# Converter_board.net
KiCad netlist of a schematic drawn in EAGLE
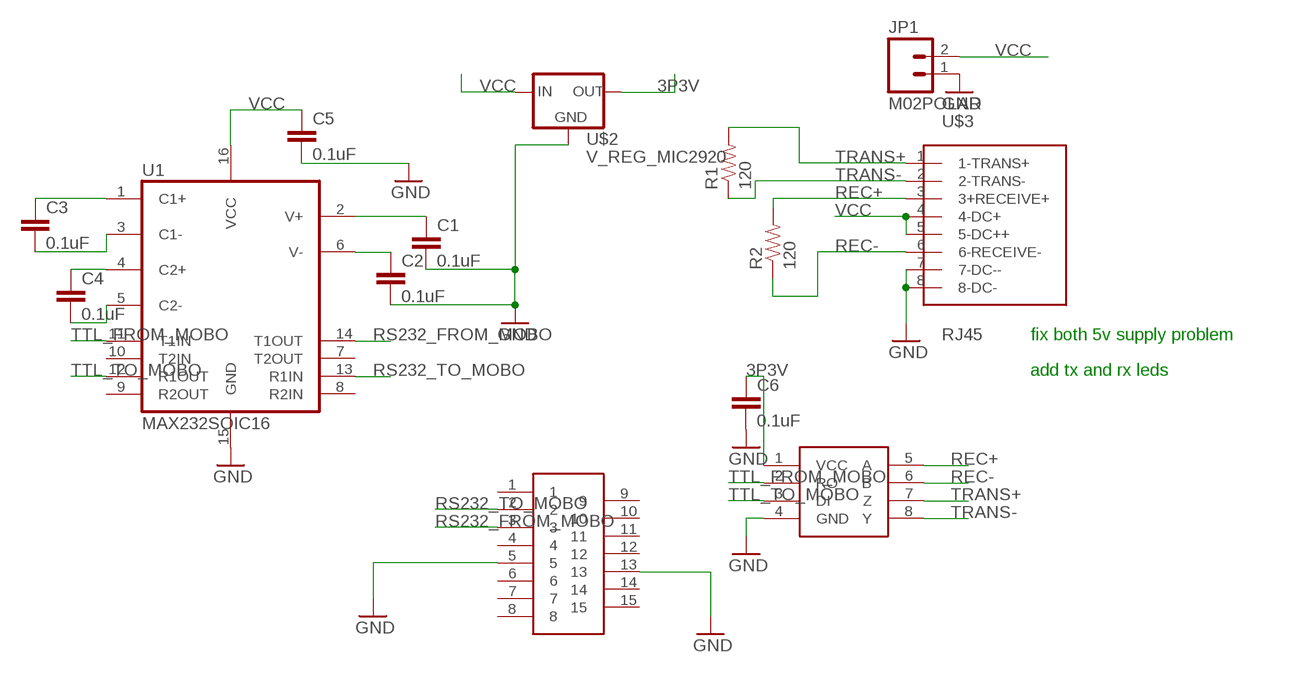
[diagram p0: schematic, sheet 1]

(export (version "E")
  (design (tool "Eeschema 10.0.6"))
  (components
    (comp (ref "C1")
      (value "0.1uF")
      (footprint "eagle-import:1206")
      (libsource (lib "eagle-import") (part "CAP1206"))
    )
    (comp (ref "C2")
      (value "0.1uF")
      (footprint "eagle-import:1206")
      (libsource (lib "eagle-import") (part "CAP1206"))
    )
    (comp (ref "C3")
      (value "0.1uF")
      (footprint "eagle-import:1206")
      (libsource (lib "eagle-import") (part "CAP1206"))
    )
    (comp (ref "C4")
      (value "0.1uF")
      (footprint "eagle-import:1206")
      (libsource (lib "eagle-import") (part "CAP1206"))
    )
    (comp (ref "C5")
      (value "0.1uF")
      (footprint "eagle-import:1206")
      (libsource (lib "eagle-import") (part "CAP1206"))
    )
    (comp (ref "C6")
      (value "0.1uF")
      (footprint "eagle-import:1206")
      (libsource (lib "eagle-import") (part "CAP1206"))
    )
    (comp (ref "JP1")
      (value "M02POLAR")
      (footprint "eagle-import:MOLEX-1X2")
      (libsource (lib "eagle-import") (part "M02POLAR"))
    )
    (comp (ref "R1")
      (value "120")
      (footprint "eagle-import:1206")
      (libsource (lib "eagle-import") (part "RESISTOR1206"))
    )
    (comp (ref "R2")
      (value "120")
      (footprint "eagle-import:1206")
      (libsource (lib "eagle-import") (part "RESISTOR1206"))
    )
    (comp (ref "U$1")
      (value "MAX3077ESA")
      (footprint "eagle-import:SOIC8")
      (libsource (lib "eagle-import") (part "MAX3077ESA"))
    )
    (comp (ref "U$2")
      (value "V_REG_MIC2920")
      (footprint "eagle-import:SOT223")
      (libsource (lib "eagle-import") (part "V_REG_MIC2920"))
    )
    (comp (ref "U$3")
      (value "RJ45")
      (footprint "eagle-import:RJ45-CAT5E")
      (libsource (lib "eagle-import") (part "RJ45"))
    )
    (comp (ref "U$4")
      (value "DB15")
      (footprint "eagle-import:DB15")
      (libsource (lib "eagle-import") (part "DB15"))
    )
    (comp (ref "U1")
      (value "MAX232SOIC16")
      (footprint "eagle-import:SO016")
      (libsource (lib "eagle-import") (part "MAX232SOIC16"))
    )
  )
  (nets
    (net (code "1") (name "/3P3V") (class "Default")
      (node (ref "C6") (pin "1") (pinfunction "1_1") (pintype "passive"))
      (node (ref "U$1") (pin "1") (pinfunction "VCC_1") (pintype "bidirectional"))
      (node (ref "U$2") (pin "3") (pinfunction "OUT_3") (pintype "output"))
    )
    (net (code "2") (name "/REC+") (class "Default")
      (node (ref "R2") (pin "2") (pinfunction "2_2") (pintype "passive"))
      (node (ref "U$1") (pin "5") (pinfunction "A_5") (pintype "bidirectional"))
      (node (ref "U$3") (pin "3") (pinfunction "3+RECEIVE+_3") (pintype "bidirectional"))
    )
    (net (code "3") (name "/REC-") (class "Default")
      (node (ref "R2") (pin "1") (pinfunction "1_1") (pintype "passive"))
      (node (ref "U$1") (pin "6") (pinfunction "B_6") (pintype "bidirectional"))
      (node (ref "U$3") (pin "6") (pinfunction "6-RECEIVE-_6") (pintype "bidirectional"))
    )
    (net (code "4") (name "/RS232_FROM_MOBO") (class "Default")
      (node (ref "U$4") (pin "3") (pinfunction "3_3") (pintype "bidirectional"))
      (node (ref "U1") (pin "14") (pinfunction "T1OUT_14") (pintype "output"))
    )
    (net (code "5") (name "/RS232_TO_MOBO") (class "Default")
      (node (ref "U$4") (pin "2") (pinfunction "2_2") (pintype "bidirectional"))
      (node (ref "U1") (pin "13") (pinfunction "R1IN_13") (pintype "input"))
    )
    (net (code "6") (name "/TRANS+") (class "Default")
      (node (ref "R1") (pin "2") (pinfunction "2_2") (pintype "passive"))
      (node (ref "U$1") (pin "7") (pinfunction "Z_7") (pintype "bidirectional"))
      (node (ref "U$3") (pin "1") (pinfunction "1-TRANS+_1") (pintype "bidirectional"))
    )
    (net (code "7") (name "/TRANS-") (class "Default")
      (node (ref "R1") (pin "1") (pinfunction "1_1") (pintype "passive"))
      (node (ref "U$1") (pin "8") (pinfunction "Y_8") (pintype "bidirectional"))
      (node (ref "U$3") (pin "2") (pinfunction "2-TRANS-_2") (pintype "bidirectional"))
    )
    (net (code "8") (name "/TTL_FROM_MOBO") (class "Default")
      (node (ref "U$1") (pin "2") (pinfunction "RO_2") (pintype "bidirectional"))
      (node (ref "U1") (pin "11") (pinfunction "T1IN_11") (pintype "input"))
    )
    (net (code "9") (name "/TTL_TO_MOBO") (class "Default")
      (node (ref "U$1") (pin "3") (pinfunction "DI_3") (pintype "bidirectional"))
      (node (ref "U1") (pin "12") (pinfunction "R1OUT_12") (pintype "output"))
    )
    (net (code "10") (name "/VCC") (class "Default")
      (node (ref "C5") (pin "1") (pinfunction "1_1") (pintype "passive"))
      (node (ref "JP1") (pin "2") (pinfunction "2_2") (pintype "passive"))
      (node (ref "U$2") (pin "1") (pinfunction "IN_1") (pintype "input"))
      (node (ref "U$3") (pin "4") (pinfunction "4-DC+_4") (pintype "bidirectional"))
      (node (ref "U$3") (pin "5") (pinfunction "5-DC++_5") (pintype "bidirectional"))
      (node (ref "U1") (pin "16") (pinfunction "VCC_16") (pintype "bidirectional"))
    )
    (net (code "11") (name "GND") (class "Default")
      (node (ref "C1") (pin "2") (pinfunction "2_2") (pintype "passive"))
      (node (ref "C2") (pin "2") (pinfunction "2_2") (pintype "passive"))
      (node (ref "C5") (pin "2") (pinfunction "2_2") (pintype "passive"))
      (node (ref "C6") (pin "2") (pinfunction "2_2") (pintype "passive"))
      (node (ref "JP1") (pin "1") (pinfunction "1_1") (pintype "passive"))
      (node (ref "U$1") (pin "4") (pinfunction "GND_4") (pintype "bidirectional"))
      (node (ref "U$2") (pin "2") (pinfunction "GND_2") (pintype "input"))
      (node (ref "U$3") (pin "7") (pinfunction "7-DC--_7") (pintype "bidirectional"))
      (node (ref "U$3") (pin "8") (pinfunction "8-DC-_8") (pintype "bidirectional"))
      (node (ref "U$4") (pin "13") (pinfunction "13_13") (pintype "bidirectional"))
      (node (ref "U$4") (pin "5") (pinfunction "5_5") (pintype "bidirectional"))
      (node (ref "U1") (pin "15") (pinfunction "GND_15") (pintype "bidirectional"))
    )
    (net (code "12") (name "Net-(U1-C1+)") (class "Default")
      (node (ref "C3") (pin "1") (pinfunction "1_1") (pintype "passive"))
      (node (ref "U1") (pin "1") (pinfunction "C1+_1") (pintype "bidirectional"))
    )
    (net (code "13") (name "Net-(U1-C1-)") (class "Default")
      (node (ref "C3") (pin "2") (pinfunction "2_2") (pintype "passive"))
      (node (ref "U1") (pin "3") (pinfunction "C1-_3") (pintype "bidirectional"))
    )
    (net (code "14") (name "Net-(U1-C2+)") (class "Default")
      (node (ref "C4") (pin "1") (pinfunction "1_1") (pintype "passive"))
      (node (ref "U1") (pin "4") (pinfunction "C2+_4") (pintype "bidirectional"))
    )
    (net (code "15") (name "Net-(U1-C2-)") (class "Default")
      (node (ref "C4") (pin "2") (pinfunction "2_2") (pintype "passive"))
      (node (ref "U1") (pin "5") (pinfunction "C2-_5") (pintype "bidirectional"))
    )
    (net (code "16") (name "Net-(U1-V+)") (class "Default")
      (node (ref "C1") (pin "1") (pinfunction "1_1") (pintype "passive"))
      (node (ref "U1") (pin "2") (pinfunction "V+_2") (pintype "bidirectional"))
    )
    (net (code "17") (name "Net-(U1-V-)") (class "Default")
      (node (ref "C2") (pin "1") (pinfunction "1_1") (pintype "passive"))
      (node (ref "U1") (pin "6") (pinfunction "V-_6") (pintype "bidirectional"))
    )
    (net (code "18") (name "unconnected-(U$4-Pad1)") (class "Default")
      (node (ref "U$4") (pin "1") (pinfunction "1_1") (pintype "bidirectional"))
    )
    (net (code "19") (name "unconnected-(U$4-Pad4)") (class "Default")
      (node (ref "U$4") (pin "4") (pinfunction "4_4") (pintype "bidirectional"))
    )
    (net (code "20") (name "unconnected-(U$4-Pad6)") (class "Default")
      (node (ref "U$4") (pin "6") (pinfunction "6_6") (pintype "bidirectional"))
    )
    (net (code "21") (name "unconnected-(U$4-Pad7)") (class "Default")
      (node (ref "U$4") (pin "7") (pinfunction "7_7") (pintype "bidirectional"))
    )
    (net (code "22") (name "unconnected-(U$4-Pad8)") (class "Default")
      (node (ref "U$4") (pin "8") (pinfunction "8_8") (pintype "bidirectional"))
    )
    (net (code "23") (name "unconnected-(U$4-Pad9)") (class "Default")
      (node (ref "U$4") (pin "9") (pinfunction "9_9") (pintype "bidirectional"))
    )
    (net (code "24") (name "unconnected-(U$4-Pad10)") (class "Default")
      (node (ref "U$4") (pin "10") (pinfunction "10_10") (pintype "bidirectional"))
    )
    (net (code "25") (name "unconnected-(U$4-Pad11)") (class "Default")
      (node (ref "U$4") (pin "11") (pinfunction "11_11") (pintype "bidirectional"))
    )
    (net (code "26") (name "unconnected-(U$4-Pad12)") (class "Default")
      (node (ref "U$4") (pin "12") (pinfunction "12_12") (pintype "bidirectional"))
    )
    (net (code "27") (name "unconnected-(U$4-Pad14)") (class "Default")
      (node (ref "U$4") (pin "14") (pinfunction "14_14") (pintype "bidirectional"))
    )
    (net (code "28") (name "unconnected-(U$4-Pad15)") (class "Default")
      (node (ref "U$4") (pin "15") (pinfunction "15_15") (pintype "bidirectional"))
    )
    (net (code "29") (name "unconnected-(U1-R2IN-Pad8)") (class "Default")
      (node (ref "U1") (pin "8") (pinfunction "R2IN_8") (pintype "input"))
    )
    (net (code "30") (name "unconnected-(U1-R2OUT-Pad9)") (class "Default")
      (node (ref "U1") (pin "9") (pinfunction "R2OUT_9") (pintype "output"))
    )
    (net (code "31") (name "unconnected-(U1-T2IN-Pad10)") (class "Default")
      (node (ref "U1") (pin "10") (pinfunction "T2IN_10") (pintype "input"))
    )
    (net (code "32") (name "unconnected-(U1-T2OUT-Pad7)") (class "Default")
      (node (ref "U1") (pin "7") (pinfunction "T2OUT_7") (pintype "output"))
    )
  )
)
